# Arduino-Headers.net
KiCad netlist of a schematic drawn in Altium Designer
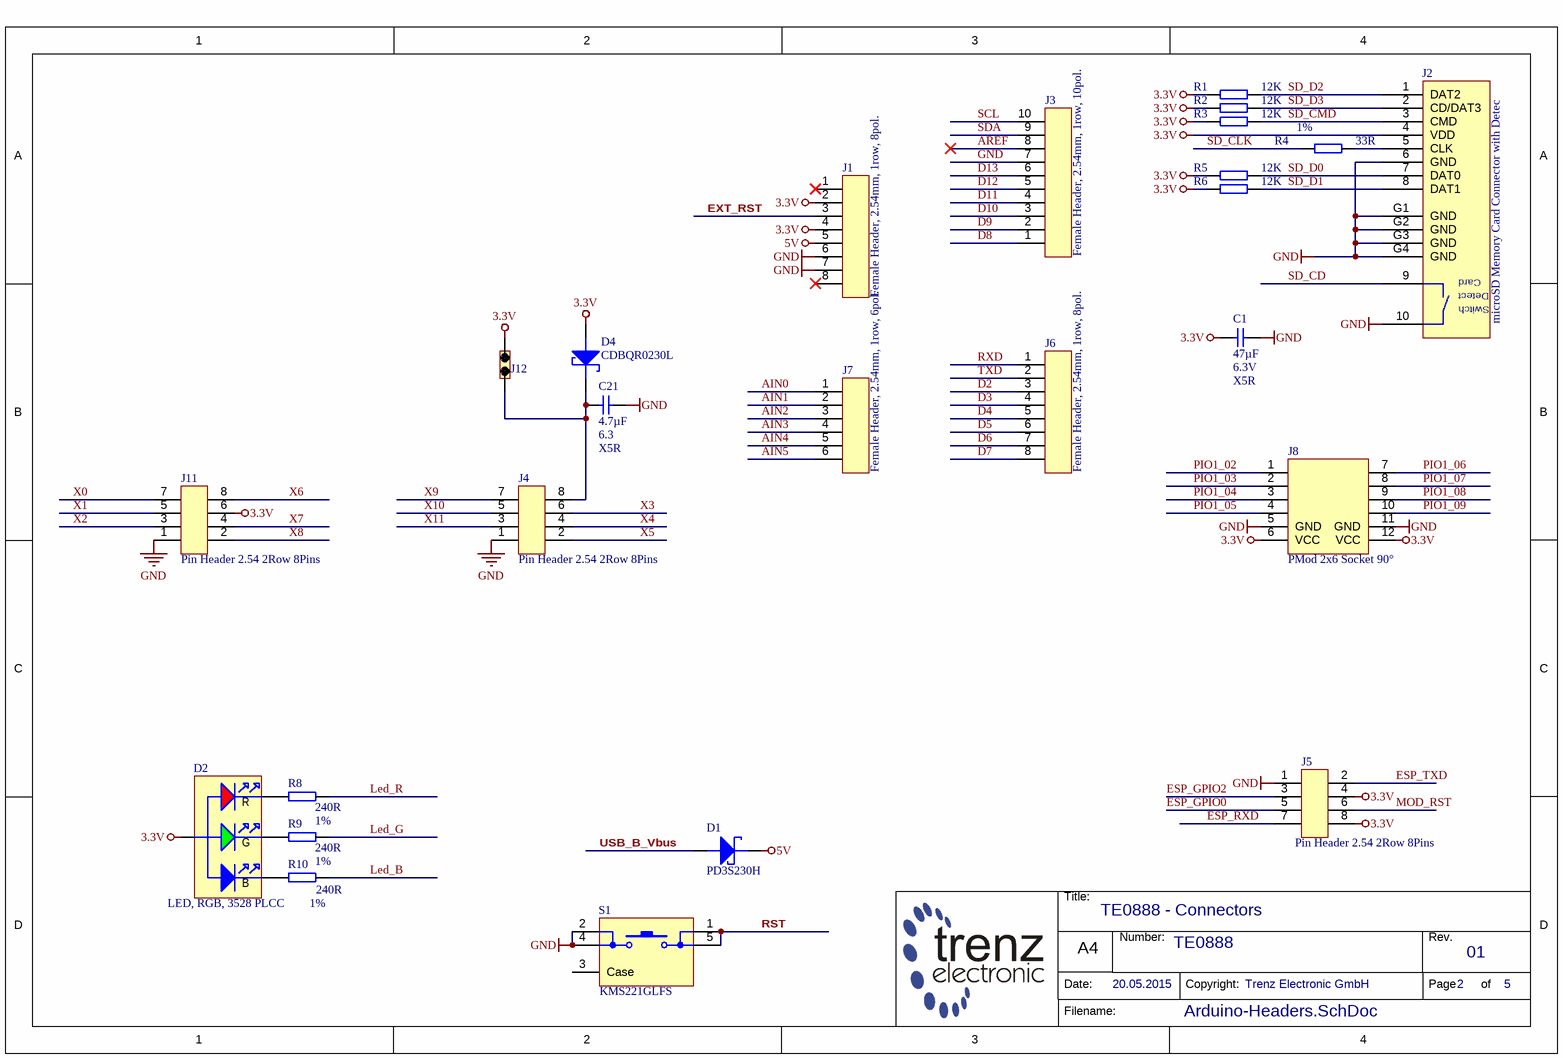
[diagram p0: Arduino-Headers.SchDoc]

(export (version "E")
  (design (tool "Eeschema 10.0.6"))
  (components
    (comp (ref "C1")
      (value "47µF")
      (footprint "CAPC2012X135N")
      (description "KON 47µF 6,3V  X5R SMD 20%")
      (fields
        (field (name "VOLTAGE") "6.3V")
        (field (name "TECHNOLOGY") "X5R")
        (field (name "TOLERANCE") "20%")
      )
      (libsource (lib "TE") (part "CAP-NP"))
    )
    (comp (ref "C21")
      (value "4.7µF")
      (footprint "CAPC1005X60N")
      (description "KON 4.7µF 6.3V X5R SMD 20%")
      (fields
        (field (name "VOLTAGE") "6.3")
        (field (name "TECHNOLOGY") "X5R")
        (field (name "TOLERANCE") "20%")
      )
      (libsource (lib "TE") (part "CAP-NP"))
    )
    (comp (ref "D1") (value "PD3S230H") (footprint "PowerDI323") (libsource (lib "TE") (part "SCHOTTKY")))
    (comp (ref "D2")
      (value "LED, RGB, 3528 PLCC")
      (footprint "PLCC150P360X280X190-4N")
      (libsource (lib "TE") (part "LED-RGB-3528"))
    )
    (comp (ref "D4")
      (value "CDBQR0230L")
      (footprint "DIOC1006X55N")
      (fields (field (name "VOLTAGE") "0.2A"))
      (libsource (lib "TE") (part "SCHOTTKY"))
    )
    (comp (ref "J1")
      (value "Female Header, 2.54mm, 1row, 8pol.")
      (footprint "BUCHSENLEISTE-2.54-8-1R")
      (description "Buchsenleiste 1 reihig präz. 8 pol.")
      (libsource (lib "") (part "CON-8_1"))
    )
    (comp (ref "J2")
      (value "microSD Memory Card Connector with Detec")
      (footprint "104031-0811")
      (description "microSD Memory Card Connector with Detect Switch")
      (libsource (lib "TE") (part "104031-0811"))
    )
    (comp (ref "J3")
      (value "Female Header, 2.54mm, 1row, 10pol.")
      (footprint "BUCHSENLEISTE-2.54-10-1R")
      (description "Buchsenleiste 1 reihig präz. 10 pol.")
      (libsource (lib "TE") (part "CON-10"))
    )
    (comp (ref "J4")
      (value "Pin Header 2.54 2Row 8Pins")
      (footprint "STIFTLEISTE2_54 OG 2R-8")
      (description "Stiftleiste gerade 2-reihig, 8pol.")
      (libsource (lib "TE") (part "CON-8"))
    )
    (comp (ref "J5")
      (value "Pin Header 2.54 2Row 8Pins")
      (footprint "STIFTLEISTE2_54 OG 2R-8")
      (description "Stiftleiste gerade 2-reihig, 8pol.")
      (libsource (lib "") (part "CON-8_2"))
    )
    (comp (ref "J6")
      (value "Female Header, 2.54mm, 1row, 8pol.")
      (footprint "BUCHSENLEISTE-2.54-8-1R")
      (description "Buchsenleiste 1 reihig präz. 8 pol.")
      (libsource (lib "") (part "CON-8_1"))
    )
    (comp (ref "J7")
      (value "Female Header, 2.54mm, 1row, 6pol.")
      (footprint "BUCHSENLEISTE-2.54-6-1R")
      (description "Buchsenleiste 1 reihig präz. 6 pol.")
      (libsource (lib "TE") (part "CON-6"))
    )
    (comp (ref "J8")
      (value "PMod 2x6 Socket 90°")
      (footprint "PMod2x6")
      (libsource (lib "TE") (part "PMod2x6"))
    )
    (comp (ref "J11")
      (value "Pin Header 2.54 2Row 8Pins")
      (footprint "STIFTLEISTE2_54 OG 2R-8")
      (description "Stiftleiste gerade 2-reihig, 8pol.")
      (libsource (lib "TE") (part "CON-8"))
    )
    (comp (ref "J12")
      (value "JUMPER2.54-2")
      (footprint "JUMPER2_54-2")
      (description "Stiftleiste gerade 1-reihig, 2pol.")
      (libsource (lib "TE") (part "JUMPER2.54-2"))
    )
    (comp (ref "R1")
      (value "12K")
      (footprint "RESC1005X40N")
      (description "WID SMD 12K 1% 0,063W")
      (libsource (lib "TE") (part "RES"))
    )
    (comp (ref "R2")
      (value "12K")
      (footprint "RESC1005X40N")
      (description "WID SMD 12K 1% 0,063W")
      (libsource (lib "TE") (part "RES"))
    )
    (comp (ref "R3")
      (value "12K")
      (footprint "RESC1005X40N")
      (description "WID SMD 12K 1% 0,063W")
      (libsource (lib "TE") (part "RES"))
    )
    (comp (ref "R4")
      (value "33R")
      (footprint "RESC0603X26N")
      (description "WID SMD 33R 1% 0,05W")
      (fields (field (name "TOLERANCE") "1%"))
      (libsource (lib "TE") (part "RES"))
    )
    (comp (ref "R5")
      (value "12K")
      (footprint "RESC1005X40N")
      (description "WID SMD 12K 1% 0,063W")
      (libsource (lib "TE") (part "RES"))
    )
    (comp (ref "R6")
      (value "12K")
      (footprint "RESC1005X40N")
      (description "WID SMD 12K 1% 0,063W")
      (libsource (lib "TE") (part "RES"))
    )
    (comp (ref "R8")
      (value "240R")
      (footprint "RESC1005X40N")
      (description "WID SMD 240R 1% 0,063W")
      (fields (field (name "TOLERANCE") "1%"))
      (libsource (lib "TE") (part "RES"))
    )
    (comp (ref "R9")
      (value "240R")
      (footprint "RESC1005X40N")
      (description "WID SMD 240R 1% 0,063W")
      (fields (field (name "TOLERANCE") "1%"))
      (libsource (lib "TE") (part "RES"))
    )
    (comp (ref "R10")
      (value "240R")
      (footprint "RESC1005X40N")
      (description "WID SMD 240R 1% 0,063W")
      (fields (field (name "TOLERANCE") "1%"))
      (libsource (lib "TE") (part "RES"))
    )
    (comp (ref "S1")
      (value "KMS221GLFS")
      (footprint "KMS2xxGLFS")
      (description "KMS221GLFS - SWITCH, SPST, 0.05A, 32VDC, SMD")
      (libsource (lib "TE") (part "KMS2xxGLFS"))
    )
  )
  (nets
    (net (code "1") (name "/AIN0") (class "Default") (node (ref "J7") (pin "1") (pintype "passive")))
    (net (code "2") (name "/AIN1") (class "Default") (node (ref "J7") (pin "2") (pintype "passive")))
    (net (code "3") (name "/AIN2") (class "Default") (node (ref "J7") (pin "3") (pintype "passive")))
    (net (code "4") (name "/AIN3") (class "Default") (node (ref "J7") (pin "4") (pintype "passive")))
    (net (code "5") (name "/AIN4") (class "Default") (node (ref "J7") (pin "5") (pintype "passive")))
    (net (code "6") (name "/AIN5") (class "Default") (node (ref "J7") (pin "6") (pintype "passive")))
    (net (code "7") (name "/AREF") (class "Default")
      (node (ref "J3") (pin "8") (pinfunction "8_8") (pintype "passive+no_connect"))
    )
    (net (code "8") (name "/D2") (class "Default") (node (ref "J6") (pin "3") (pintype "passive")))
    (net (code "9") (name "/D3") (class "Default") (node (ref "J6") (pin "4") (pintype "passive")))
    (net (code "10") (name "/D4") (class "Default") (node (ref "J6") (pin "5") (pintype "passive")))
    (net (code "11") (name "/D5") (class "Default") (node (ref "J6") (pin "6") (pintype "passive")))
    (net (code "12") (name "/D6") (class "Default") (node (ref "J6") (pin "7") (pintype "passive")))
    (net (code "13") (name "/D7") (class "Default") (node (ref "J6") (pin "8") (pintype "passive")))
    (net (code "14") (name "/D8") (class "Default")
      (node (ref "J3") (pin "1") (pinfunction "1_1") (pintype "passive"))
    )
    (net (code "15") (name "/D9") (class "Default")
      (node (ref "J3") (pin "2") (pinfunction "2_2") (pintype "passive"))
    )
    (net (code "16") (name "/D10") (class "Default")
      (node (ref "J3") (pin "3") (pinfunction "3_3") (pintype "passive"))
    )
    (net (code "17") (name "/D11") (class "Default")
      (node (ref "J3") (pin "4") (pinfunction "4_4") (pintype "passive"))
    )
    (net (code "18") (name "/D12") (class "Default")
      (node (ref "J3") (pin "5") (pinfunction "5_5") (pintype "passive"))
    )
    (net (code "19") (name "/D13") (class "Default")
      (node (ref "J3") (pin "6") (pinfunction "6_6") (pintype "passive"))
    )
    (net (code "20") (name "/ESP_GPIO0") (class "Default") (node (ref "J5") (pin "5") (pintype "passive")))
    (net (code "21") (name "/ESP_GPIO2") (class "Default") (node (ref "J5") (pin "3") (pintype "passive")))
    (net (code "22") (name "/ESP_RXD") (class "Default") (node (ref "J5") (pin "7") (pintype "passive")))
    (net (code "23") (name "/ESP_TXD") (class "Default") (node (ref "J5") (pin "2") (pintype "passive")))
    (net (code "24") (name "/EXT_RST") (class "Default") (node (ref "J1") (pin "3") (pintype "passive")))
    (net (code "25") (name "/Led_B") (class "Default")
      (node (ref "R10") (pin "1") (pinfunction "1_1") (pintype "passive"))
    )
    (net (code "26") (name "/Led_G") (class "Default")
      (node (ref "R9") (pin "1") (pinfunction "1_1") (pintype "passive"))
    )
    (net (code "27") (name "/Led_R") (class "Default")
      (node (ref "R8") (pin "1") (pinfunction "1_1") (pintype "passive"))
    )
    (net (code "28") (name "/MOD_RST") (class "Default") (node (ref "J5") (pin "6") (pintype "passive")))
    (net (code "29") (name "/PIO1_02") (class "Default") (node (ref "J8") (pin "1") (pintype "passive")))
    (net (code "30") (name "/PIO1_03") (class "Default") (node (ref "J8") (pin "2") (pintype "passive")))
    (net (code "31") (name "/PIO1_04") (class "Default") (node (ref "J8") (pin "3") (pintype "passive")))
    (net (code "32") (name "/PIO1_05") (class "Default") (node (ref "J8") (pin "4") (pintype "passive")))
    (net (code "33") (name "/PIO1_06") (class "Default") (node (ref "J8") (pin "7") (pintype "passive")))
    (net (code "34") (name "/PIO1_07") (class "Default") (node (ref "J8") (pin "8") (pintype "passive")))
    (net (code "35") (name "/PIO1_08") (class "Default") (node (ref "J8") (pin "9") (pintype "passive")))
    (net (code "36") (name "/PIO1_09") (class "Default") (node (ref "J8") (pin "10") (pintype "passive")))
    (net (code "37") (name "/RST") (class "Default")
      (node (ref "S1") (pin "1") (pinfunction "1_1") (pintype "passive"))
      (node (ref "S1") (pin "5") (pinfunction "5_5") (pintype "passive"))
    )
    (net (code "38") (name "/RXD") (class "Default") (node (ref "J6") (pin "1") (pintype "passive")))
    (net (code "39") (name "/SCL") (class "Default")
      (node (ref "J3") (pin "10") (pinfunction "10_10") (pintype "passive"))
    )
    (net (code "40") (name "/SDA") (class "Default")
      (node (ref "J3") (pin "9") (pinfunction "9_9") (pintype "passive"))
    )
    (net (code "41") (name "/SD_CD") (class "Default")
      (node (ref "J2") (pin "9") (pinfunction "CDSW_9") (pintype "passive"))
    )
    (net (code "42") (name "/SD_CLK") (class "Default")
      (node (ref "R4") (pin "1") (pinfunction "1_1") (pintype "passive"))
    )
    (net (code "43") (name "/SD_CMD") (class "Default")
      (node (ref "J2") (pin "3") (pinfunction "CMD_3") (pintype "passive"))
      (node (ref "R3") (pin "2") (pinfunction "2_2") (pintype "passive"))
    )
    (net (code "44") (name "/SD_D0") (class "Default")
      (node (ref "J2") (pin "7") (pinfunction "DAT0_7") (pintype "passive"))
      (node (ref "R5") (pin "2") (pinfunction "2_2") (pintype "passive"))
    )
    (net (code "45") (name "/SD_D1") (class "Default")
      (node (ref "J2") (pin "8") (pinfunction "DAT1_8") (pintype "passive"))
      (node (ref "R6") (pin "2") (pinfunction "2_2") (pintype "passive"))
    )
    (net (code "46") (name "/SD_D2") (class "Default")
      (node (ref "J2") (pin "1") (pinfunction "DAT2_1") (pintype "passive"))
      (node (ref "R1") (pin "2") (pinfunction "2_2") (pintype "passive"))
    )
    (net (code "47") (name "/SD_D3") (class "Default")
      (node (ref "J2") (pin "2") (pinfunction "CD/DAT3_2") (pintype "passive"))
      (node (ref "R2") (pin "2") (pinfunction "2_2") (pintype "passive"))
    )
    (net (code "48") (name "/TXD") (class "Default") (node (ref "J6") (pin "2") (pintype "passive")))
    (net (code "49") (name "/USB_B_Vbus") (class "Default")
      (node (ref "D1") (pin "2") (pinfunction "ANODE_2") (pintype "passive"))
    )
    (net (code "50") (name "/X0") (class "Default") (node (ref "J11") (pin "7") (pintype "passive")))
    (net (code "51") (name "/X1") (class "Default") (node (ref "J11") (pin "5") (pintype "passive")))
    (net (code "52") (name "/X2") (class "Default") (node (ref "J11") (pin "3") (pintype "passive")))
    (net (code "53") (name "/X3") (class "Default") (node (ref "J4") (pin "6") (pintype "passive")))
    (net (code "54") (name "/X4") (class "Default") (node (ref "J4") (pin "4") (pintype "passive")))
    (net (code "55") (name "/X5") (class "Default") (node (ref "J4") (pin "2") (pintype "passive")))
    (net (code "56") (name "/X6") (class "Default") (node (ref "J11") (pin "8") (pintype "passive")))
    (net (code "57") (name "/X7") (class "Default") (node (ref "J11") (pin "4") (pintype "passive")))
    (net (code "58") (name "/X8") (class "Default") (node (ref "J11") (pin "2") (pintype "passive")))
    (net (code "59") (name "/X9") (class "Default") (node (ref "J4") (pin "7") (pintype "passive")))
    (net (code "60") (name "/X10") (class "Default") (node (ref "J4") (pin "5") (pintype "passive")))
    (net (code "61") (name "/X11") (class "Default") (node (ref "J4") (pin "3") (pintype "passive")))
    (net (code "62") (name "3.3V") (class "Default")
      (node (ref "C1") (pin "1") (pinfunction "1_1") (pintype "passive"))
      (node (ref "D2") (pin "3") (pinfunction "ANODE_3") (pintype "passive"))
      (node (ref "D4") (pin "2") (pinfunction "ANODE_2") (pintype "passive"))
      (node (ref "J1") (pin "2") (pintype "passive"))
      (node (ref "J1") (pin "4") (pintype "passive"))
      (node (ref "J11") (pin "6") (pintype "passive"))
      (node (ref "J12") (pin "1") (pinfunction "1_1") (pintype "passive"))
      (node (ref "J2") (pin "4") (pinfunction "VDD_4") (pintype "passive"))
      (node (ref "J5") (pin "4") (pintype "passive"))
      (node (ref "J5") (pin "8") (pintype "passive"))
      (node (ref "J8") (pin "12") (pinfunction "VCC_12") (pintype "power_in"))
      (node (ref "J8") (pin "6") (pinfunction "VCC_6") (pintype "power_in"))
      (node (ref "R1") (pin "1") (pinfunction "1_1") (pintype "passive"))
      (node (ref "R2") (pin "1") (pinfunction "1_1") (pintype "passive"))
      (node (ref "R3") (pin "1") (pinfunction "1_1") (pintype "passive"))
      (node (ref "R5") (pin "1") (pinfunction "1_1") (pintype "passive"))
      (node (ref "R6") (pin "1") (pinfunction "1_1") (pintype "passive"))
    )
    (net (code "63") (name "5V") (class "Default")
      (node (ref "D1") (pin "1") (pinfunction "KATHODE_1") (pintype "passive"))
      (node (ref "J1") (pin "5") (pintype "passive"))
    )
    (net (code "64") (name "GND") (class "Default")
      (node (ref "C1") (pin "2") (pinfunction "2_2") (pintype "passive"))
      (node (ref "C21") (pin "1") (pinfunction "1_1") (pintype "passive"))
      (node (ref "J1") (pin "6") (pintype "passive"))
      (node (ref "J1") (pin "7") (pintype "passive"))
      (node (ref "J11") (pin "1") (pintype "passive"))
      (node (ref "J2") (pin "10") (pinfunction "CDSW_10") (pintype "passive"))
      (node (ref "J2") (pin "6") (pinfunction "GND_6") (pintype "passive"))
      (node (ref "J2") (pin "G1") (pinfunction "GND_G1") (pintype "passive"))
      (node (ref "J2") (pin "G2") (pinfunction "GND_G2") (pintype "passive"))
      (node (ref "J2") (pin "G3") (pinfunction "GND_G3") (pintype "passive"))
      (node (ref "J2") (pin "G4") (pinfunction "GND_G4") (pintype "passive"))
      (node (ref "J3") (pin "7") (pinfunction "7_7") (pintype "passive"))
      (node (ref "J4") (pin "1") (pintype "passive"))
      (node (ref "J5") (pin "1") (pintype "passive"))
      (node (ref "J8") (pin "11") (pinfunction "GND_11") (pintype "power_in"))
      (node (ref "J8") (pin "5") (pinfunction "GND_5") (pintype "power_in"))
      (node (ref "S1") (pin "2") (pinfunction "2_2") (pintype "passive"))
      (node (ref "S1") (pin "4") (pinfunction "4_4") (pintype "passive"))
    )
    (net (code "65") (name "Net-(D2-BLUE)") (class "Default")
      (node (ref "D2") (pin "4") (pinfunction "BLUE_4") (pintype "passive"))
      (node (ref "R10") (pin "2") (pinfunction "2_2") (pintype "passive"))
    )
    (net (code "66") (name "Net-(D2-GREEN)") (class "Default")
      (node (ref "D2") (pin "2") (pinfunction "GREEN_2") (pintype "passive"))
      (node (ref "R9") (pin "2") (pinfunction "2_2") (pintype "passive"))
    )
    (net (code "67") (name "Net-(D2-RED)") (class "Default")
      (node (ref "D2") (pin "1") (pinfunction "RED_1") (pintype "passive"))
      (node (ref "R8") (pin "2") (pinfunction "2_2") (pintype "passive"))
    )
    (net (code "68") (name "Net-(D4-KATHODE)") (class "Default")
      (node (ref "C21") (pin "2") (pinfunction "2_2") (pintype "passive"))
      (node (ref "D4") (pin "1") (pinfunction "KATHODE_1") (pintype "passive"))
      (node (ref "J12") (pin "2") (pinfunction "2_2") (pintype "passive"))
      (node (ref "J4") (pin "8") (pintype "passive"))
    )
    (net (code "69") (name "Net-(J2-CLK)") (class "Default")
      (node (ref "J2") (pin "5") (pinfunction "CLK_5") (pintype "passive"))
      (node (ref "R4") (pin "2") (pinfunction "2_2") (pintype "passive"))
    )
    (net (code "70") (name "unconnected-(J1-Pad1)") (class "Default")
      (node (ref "J1") (pin "1") (pintype "passive+no_connect"))
    )
    (net (code "71") (name "unconnected-(J1-Pad8)") (class "Default")
      (node (ref "J1") (pin "8") (pintype "passive+no_connect"))
    )
    (net (code "72") (name "unconnected-(S1-Case-Pad3)") (class "Default")
      (node (ref "S1") (pin "3") (pinfunction "Case_3") (pintype "passive"))
    )
  )
)
